# 3DPrinter-mainboard.net
KiCad netlist of a schematic drawn in EAGLE
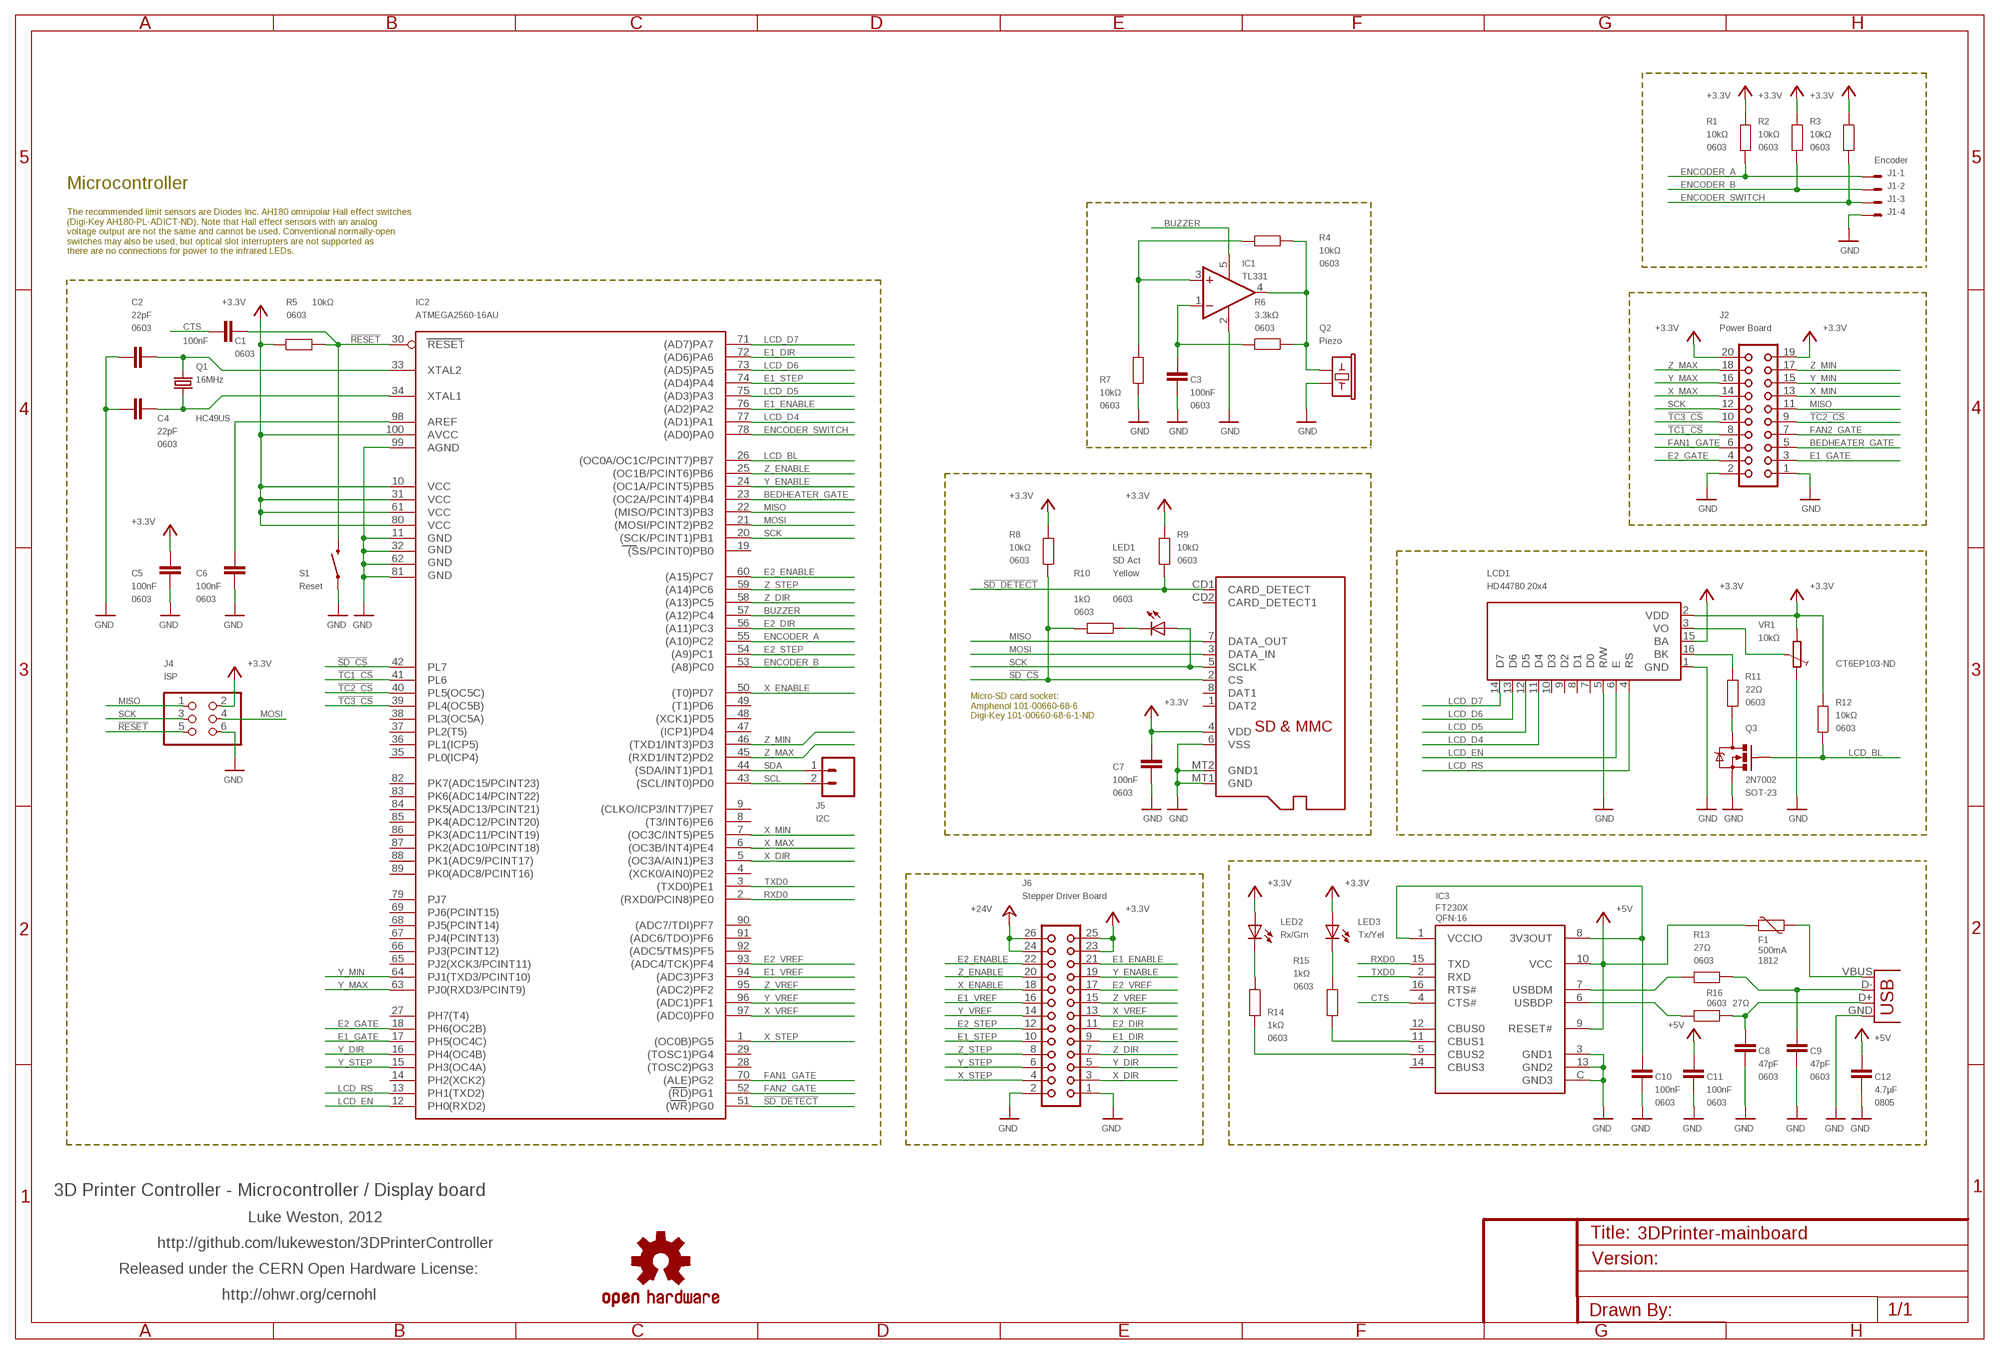
[diagram p0: schematic, sheet 1]

(export (version "E")
  (design (tool "Eeschema 10.0.6"))
  (components
    (comp (ref "C1")
      (value "100nF")
      (footprint "eagle-import:0603")
      (fields (field (name "PACKAGE") "0603"))
      (libsource (lib "eagle-import") (part "CAP0603"))
    )
    (comp (ref "C2")
      (value "22pF")
      (footprint "eagle-import:0603")
      (fields (field (name "PACKAGE") "0603"))
      (libsource (lib "eagle-import") (part "CAP0603"))
    )
    (comp (ref "C3")
      (value "100nF")
      (footprint "eagle-import:0603")
      (fields (field (name "PACKAGE") "0603"))
      (libsource (lib "eagle-import") (part "CAP0603"))
    )
    (comp (ref "C4")
      (value "22pF")
      (footprint "eagle-import:0603")
      (fields (field (name "PACKAGE") "0603"))
      (libsource (lib "eagle-import") (part "CAP0603"))
    )
    (comp (ref "C5")
      (value "100nF")
      (footprint "eagle-import:0603")
      (fields (field (name "PACKAGE") "0603"))
      (libsource (lib "eagle-import") (part "CAP0603"))
    )
    (comp (ref "C6")
      (value "100nF")
      (footprint "eagle-import:0603")
      (fields (field (name "PACKAGE") "0603"))
      (libsource (lib "eagle-import") (part "CAP0603"))
    )
    (comp (ref "C7")
      (value "100nF")
      (footprint "eagle-import:0603")
      (fields (field (name "PACKAGE") "0603"))
      (libsource (lib "eagle-import") (part "CAP0603"))
    )
    (comp (ref "C8")
      (value "47pF")
      (footprint "eagle-import:0603")
      (fields (field (name "PACKAGE") "0603"))
      (libsource (lib "eagle-import") (part "CAP0603"))
    )
    (comp (ref "C9")
      (value "47pF")
      (footprint "eagle-import:0603")
      (fields (field (name "PACKAGE") "0603"))
      (libsource (lib "eagle-import") (part "CAP0603"))
    )
    (comp (ref "C10")
      (value "100nF")
      (footprint "eagle-import:0603")
      (fields (field (name "PACKAGE") "0603"))
      (libsource (lib "eagle-import") (part "CAP0603"))
    )
    (comp (ref "C11")
      (value "100nF")
      (footprint "eagle-import:0603")
      (fields (field (name "PACKAGE") "0603"))
      (libsource (lib "eagle-import") (part "CAP0603"))
    )
    (comp (ref "C12")
      (value "4.7µF")
      (footprint "eagle-import:0805")
      (fields (field (name "PACKAGE") "0805"))
      (libsource (lib "eagle-import") (part "CAP0805"))
    )
    (comp (ref "F1")
      (value "500mA")
      (footprint "eagle-import:1812")
      (fields (field (name "PACKAGE") "1812"))
      (libsource (lib "eagle-import") (part "PTC"))
    )
    (comp (ref "IC1")
      (value "TL331")
      (footprint "eagle-import:DBV-R-PDSO-G5")
      (libsource (lib "eagle-import") (part "TL331"))
    )
    (comp (ref "IC2")
      (value "ATMEGA2560-16AU")
      (footprint "eagle-import:TQFP100")
      (libsource (lib "eagle-import") (part "ATMEGAAU1280-16"))
    )
    (comp (ref "IC3")
      (value "FT230X")
      (footprint "eagle-import:QFN4X4-16")
      (fields (field (name "PACKAGE") "QFN-16"))
      (libsource (lib "eagle-import") (part "FT230XQ"))
    )
    (comp (ref "J1")
      (value "Encoder")
      (footprint "eagle-import:7395-04")
      (libsource (lib "eagle-import") (part "22-?-0405-7048"))
    )
    (comp (ref "J2")
      (value "Power Board")
      (footprint "eagle-import:CON20L")
      (fields (field (name "OC_FARNELL") "unknown") (field (name "OC_NEWARK") "unknown"))
      (libsource (lib "eagle-import") (part "CON20L"))
    )
    (comp (ref "J3")
      (value "MicroSD Card")
      (footprint "eagle-import:ADAFRUIT_MICROSD")
      (libsource (lib "eagle-import") (part "ADAFRUIT_MICROSD"))
    )
    (comp (ref "J4")
      (value "ISP")
      (footprint "eagle-import:2X03")
      (libsource (lib "eagle-import") (part "PINHD-2X3"))
    )
    (comp (ref "J5")
      (value "I2C")
      (footprint "eagle-import:1X02")
      (libsource (lib "eagle-import") (part "M02PTH"))
    )
    (comp (ref "J6")
      (value "Stepper Driver Board")
      (footprint "eagle-import:CON26L")
      (libsource (lib "eagle-import") (part "CON26L"))
    )
    (comp (ref "LCD1")
      (value "HD44780 20x4")
      (footprint "eagle-import:HDM20416L")
      (libsource (lib "eagle-import") (part "HDM20416L"))
    )
    (comp (ref "LED1")
      (value "SD Act")
      (footprint "eagle-import:LED-0603")
      (fields (field (name "COLOUR") "Yellow") (field (name "PACKAGE") "0603"))
      (libsource (lib "eagle-import") (part "LED0603"))
    )
    (comp (ref "LED2")
      (value "Rx/Grn")
      (footprint "eagle-import:LED-0603")
      (libsource (lib "eagle-import") (part "LED0603"))
    )
    (comp (ref "LED3")
      (value "Tx/Yel")
      (footprint "eagle-import:LED-0603")
      (libsource (lib "eagle-import") (part "LED0603"))
    )
    (comp (ref "Q1")
      (value "16MHz")
      (footprint "eagle-import:HC49US")
      (fields (field (name "PACKAGE") "HC49US"))
      (libsource (lib "eagle-import") (part "CRYSTALHC49US"))
    )
    (comp (ref "Q2")
      (value "Piezo")
      (footprint "eagle-import:FREETRONICS-MASTER-V1_BUZZER-12X12-SMT")
      (libsource (lib "eagle-import") (part "FREETRONICS-MASTER-V1_BUZZERSMD12X12"))
    )
    (comp (ref "Q3")
      (value "2N7002")
      (footprint "eagle-import:SOT23-3")
      (fields (field (name "PACKAGE") "SOT-23"))
      (libsource (lib "eagle-import") (part "MOSFET-NCHANNELSMD"))
    )
    (comp (ref "R1")
      (value "10kΩ")
      (footprint "eagle-import:0603")
      (fields (field (name "PACKAGE") "0603"))
      (libsource (lib "eagle-import") (part "RESISTOR0603"))
    )
    (comp (ref "R2")
      (value "10kΩ")
      (footprint "eagle-import:0603")
      (fields (field (name "PACKAGE") "0603"))
      (libsource (lib "eagle-import") (part "RESISTOR0603"))
    )
    (comp (ref "R3")
      (value "10kΩ")
      (footprint "eagle-import:0603")
      (fields (field (name "PACKAGE") "0603"))
      (libsource (lib "eagle-import") (part "RESISTOR0603"))
    )
    (comp (ref "R4")
      (value "10kΩ")
      (footprint "eagle-import:0603")
      (fields (field (name "PACKAGE") "0603"))
      (libsource (lib "eagle-import") (part "RESISTOR0603"))
    )
    (comp (ref "R5")
      (value "10kΩ")
      (footprint "eagle-import:0603")
      (fields (field (name "PACKAGE") "0603"))
      (libsource (lib "eagle-import") (part "RESISTOR0603"))
    )
    (comp (ref "R6")
      (value "3.3kΩ")
      (footprint "eagle-import:0603")
      (fields (field (name "PACKAGE") "0603"))
      (libsource (lib "eagle-import") (part "RESISTOR0603"))
    )
    (comp (ref "R7")
      (value "10kΩ")
      (footprint "eagle-import:0603")
      (fields (field (name "PACKAGE") "0603"))
      (libsource (lib "eagle-import") (part "RESISTOR0603"))
    )
    (comp (ref "R8")
      (value "10kΩ")
      (footprint "eagle-import:0603")
      (fields (field (name "PACKAGE") "0603"))
      (libsource (lib "eagle-import") (part "RESISTOR0603"))
    )
    (comp (ref "R9")
      (value "10kΩ")
      (footprint "eagle-import:0603")
      (fields (field (name "PACKAGE") "0603"))
      (libsource (lib "eagle-import") (part "RESISTOR0603"))
    )
    (comp (ref "R10")
      (value "1kΩ")
      (footprint "eagle-import:0603")
      (fields (field (name "PACKAGE") "0603"))
      (libsource (lib "eagle-import") (part "RESISTOR0603"))
    )
    (comp (ref "R11")
      (value "22Ω")
      (footprint "eagle-import:0603")
      (fields (field (name "PACKAGE") "0603"))
      (libsource (lib "eagle-import") (part "RESISTOR0603"))
    )
    (comp (ref "R12")
      (value "10kΩ")
      (footprint "eagle-import:0603")
      (fields (field (name "PACKAGE") "0603"))
      (libsource (lib "eagle-import") (part "RESISTOR0603"))
    )
    (comp (ref "R13")
      (value "27Ω")
      (footprint "eagle-import:0603")
      (fields (field (name "PACKAGE") "0603"))
      (libsource (lib "eagle-import") (part "RESISTOR0603"))
    )
    (comp (ref "R14")
      (value "1kΩ")
      (footprint "eagle-import:0603")
      (fields (field (name "PACKAGE") "0603"))
      (libsource (lib "eagle-import") (part "RESISTOR0603"))
    )
    (comp (ref "R15")
      (value "1kΩ")
      (footprint "eagle-import:0603")
      (fields (field (name "PACKAGE") "0603"))
      (libsource (lib "eagle-import") (part "RESISTOR0603"))
    )
    (comp (ref "R16")
      (value "27Ω")
      (footprint "eagle-import:0603")
      (fields (field (name "PACKAGE") "0603"))
      (libsource (lib "eagle-import") (part "RESISTOR0603"))
    )
    (comp (ref "S1")
      (value "Reset")
      (footprint "eagle-import:TACTILE_SWITCH_SMD")
      (libsource (lib "eagle-import") (part "SWITCH-MOMENTARY-2SMD"))
    )
    (comp (ref "SY")
      (value "OSHW-LOGOS")
      (footprint "eagle-import:OSHW-LOGO-S")
      (libsource (lib "eagle-import") (part "OSHW-LOGOS"))
    )
    (comp (ref "VR1")
      (value "10kΩ")
      (footprint "eagle-import:CT6")
      (fields (field (name "SKU") "CT6EP103-ND"))
      (libsource (lib "eagle-import") (part "TRIM_EU-CT6"))
    )
    (comp (ref "X1")
      (value "USB-MICROB")
      (footprint "eagle-import:USB-MICROB")
      (libsource (lib "eagle-import") (part "USB-MICROB"))
    )
  )
  (nets
    (net (code "1") (name "+3.3V") (class "Default")
      (node (ref "C5") (pin "1") (pinfunction "1_1") (pintype "passive"))
      (node (ref "C7") (pin "1") (pinfunction "1_1") (pintype "passive"))
      (node (ref "IC2") (pin "10") (pinfunction "VCC_10") (pintype "power_in"))
      (node (ref "IC2") (pin "100") (pinfunction "AVCC_100") (pintype "power_in"))
      (node (ref "IC2") (pin "31") (pinfunction "VCC1_31") (pintype "power_in"))
      (node (ref "IC2") (pin "61") (pinfunction "VCC2_61") (pintype "power_in"))
      (node (ref "IC2") (pin "80") (pinfunction "VCC3_80") (pintype "power_in"))
      (node (ref "J2") (pin "19") (pinfunction "19_19") (pintype "passive"))
      (node (ref "J2") (pin "20") (pinfunction "20_20") (pintype "passive"))
      (node (ref "J3") (pin "4") (pinfunction "VDD_4") (pintype "power_in"))
      (node (ref "J4") (pin "2") (pinfunction "2_2") (pintype "passive"))
      (node (ref "J6") (pin "23") (pinfunction "23_23") (pintype "passive"))
      (node (ref "J6") (pin "25") (pinfunction "25_25") (pintype "passive"))
      (node (ref "LCD1") (pin "15") (pinfunction "BA_15") (pintype "bidirectional"))
      (node (ref "LCD1") (pin "2") (pinfunction "VDD_2") (pintype "bidirectional"))
      (node (ref "LED2") (pin "A") (pinfunction "A_A") (pintype "passive"))
      (node (ref "LED3") (pin "A") (pinfunction "A_A") (pintype "passive"))
      (node (ref "R1") (pin "1") (pinfunction "1_1") (pintype "passive"))
      (node (ref "R12") (pin "1") (pinfunction "1_1") (pintype "passive"))
      (node (ref "R2") (pin "1") (pinfunction "1_1") (pintype "passive"))
      (node (ref "R3") (pin "1") (pinfunction "1_1") (pintype "passive"))
      (node (ref "R5") (pin "1") (pinfunction "1_1") (pintype "passive"))
      (node (ref "R8") (pin "1") (pinfunction "1_1") (pintype "passive"))
      (node (ref "R9") (pin "1") (pinfunction "1_1") (pintype "passive"))
      (node (ref "VR1") (pin "A") (pinfunction "A_A") (pintype "passive"))
    )
    (net (code "2") (name "+5V") (class "Default")
      (node (ref "C11") (pin "1") (pinfunction "1_1") (pintype "passive"))
      (node (ref "C12") (pin "1") (pinfunction "1_1") (pintype "passive"))
      (node (ref "F1") (pin "2") (pinfunction "P$2_2") (pintype "bidirectional"))
      (node (ref "IC3") (pin "10") (pinfunction "VCC_10") (pintype "power_in"))
      (node (ref "IC3") (pin "9") (pinfunction "RESET#_9") (pintype "input"))
    )
    (net (code "3") (name "+24V") (class "Default")
      (node (ref "J6") (pin "24") (pinfunction "24_24") (pintype "passive"))
      (node (ref "J6") (pin "26") (pinfunction "26_26") (pintype "passive"))
    )
    (net (code "4") (name "/BEDHEATER_GATE") (class "Default")
      (node (ref "IC2") (pin "23") (pinfunction "(OC2A/PCINT4)PB4_23") (pintype "bidirectional"))
      (node (ref "J2") (pin "5") (pinfunction "5_5") (pintype "passive"))
    )
    (net (code "5") (name "/BUZZER") (class "Default")
      (node (ref "IC1") (pin "5") (pinfunction "V+_5") (pintype "power_in"))
      (node (ref "IC2") (pin "57") (pinfunction "(A12)PC4_57") (pintype "bidirectional"))
    )
    (net (code "6") (name "/CTS") (class "Default")
      (node (ref "C1") (pin "1") (pinfunction "1_1") (pintype "passive"))
      (node (ref "IC3") (pin "4") (pinfunction "CTS#_4") (pintype "bidirectional"))
    )
    (net (code "7") (name "/E1_DIR") (class "Default")
      (node (ref "IC2") (pin "72") (pinfunction "(AD6)PA6_72") (pintype "bidirectional"))
      (node (ref "J6") (pin "9") (pinfunction "9_9") (pintype "passive"))
    )
    (net (code "8") (name "/E1_ENABLE") (class "Default")
      (node (ref "IC2") (pin "76") (pinfunction "(AD2)PA2_76") (pintype "bidirectional"))
      (node (ref "J6") (pin "21") (pinfunction "21_21") (pintype "passive"))
    )
    (net (code "9") (name "/E1_GATE") (class "Default")
      (node (ref "IC2") (pin "17") (pinfunction "PH5(OC4C)_17") (pintype "bidirectional"))
      (node (ref "J2") (pin "3") (pinfunction "3_3") (pintype "passive"))
    )
    (net (code "10") (name "/E1_STEP") (class "Default")
      (node (ref "IC2") (pin "74") (pinfunction "(AD4)PA4_74") (pintype "bidirectional"))
      (node (ref "J6") (pin "10") (pinfunction "10_10") (pintype "passive"))
    )
    (net (code "11") (name "/E1_VREF") (class "Default")
      (node (ref "IC2") (pin "94") (pinfunction "(ADC3)PF3_94") (pintype "bidirectional"))
      (node (ref "J6") (pin "16") (pinfunction "16_16") (pintype "passive"))
    )
    (net (code "12") (name "/E2_DIR") (class "Default")
      (node (ref "IC2") (pin "56") (pinfunction "(A11)PC3_56") (pintype "bidirectional"))
      (node (ref "J6") (pin "11") (pinfunction "11_11") (pintype "passive"))
    )
    (net (code "13") (name "/E2_ENABLE") (class "Default")
      (node (ref "IC2") (pin "60") (pinfunction "(A15)PC7_60") (pintype "bidirectional"))
      (node (ref "J6") (pin "22") (pinfunction "22_22") (pintype "passive"))
    )
    (net (code "14") (name "/E2_GATE") (class "Default")
      (node (ref "IC2") (pin "18") (pinfunction "PH6(OC2B)_18") (pintype "bidirectional"))
      (node (ref "J2") (pin "4") (pinfunction "4_4") (pintype "passive"))
    )
    (net (code "15") (name "/E2_STEP") (class "Default")
      (node (ref "IC2") (pin "54") (pinfunction "(A9)PC1_54") (pintype "bidirectional"))
      (node (ref "J6") (pin "12") (pinfunction "12_12") (pintype "passive"))
    )
    (net (code "16") (name "/E2_VREF") (class "Default")
      (node (ref "IC2") (pin "93") (pinfunction "(ADC4/TCK)PF4_93") (pintype "bidirectional"))
      (node (ref "J6") (pin "17") (pinfunction "17_17") (pintype "passive"))
    )
    (net (code "17") (name "/ENCODER_A") (class "Default")
      (node (ref "IC2") (pin "55") (pinfunction "(A10)PC2_55") (pintype "bidirectional"))
      (node (ref "J1") (pin "1") (pinfunction "S_1") (pintype "passive"))
      (node (ref "R1") (pin "2") (pinfunction "2_2") (pintype "passive"))
    )
    (net (code "18") (name "/ENCODER_B") (class "Default")
      (node (ref "IC2") (pin "53") (pinfunction "(A8)PC0_53") (pintype "bidirectional"))
      (node (ref "J1") (pin "2") (pinfunction "S_2") (pintype "passive"))
      (node (ref "R2") (pin "2") (pinfunction "2_2") (pintype "passive"))
    )
    (net (code "19") (name "/ENCODER_SWITCH") (class "Default")
      (node (ref "IC2") (pin "78") (pinfunction "(AD0)PA0_78") (pintype "bidirectional"))
      (node (ref "J1") (pin "3") (pinfunction "S_3") (pintype "passive"))
      (node (ref "R3") (pin "2") (pinfunction "2_2") (pintype "passive"))
    )
    (net (code "20") (name "/FAN1_GATE") (class "Default")
      (node (ref "IC2") (pin "70") (pinfunction "(ALE)PG2_70") (pintype "bidirectional"))
      (node (ref "J2") (pin "6") (pinfunction "6_6") (pintype "passive"))
    )
    (net (code "21") (name "/FAN2_GATE") (class "Default")
      (node (ref "IC2") (pin "52") (pinfunction "(RD)PG1_52") (pintype "bidirectional"))
      (node (ref "J2") (pin "7") (pinfunction "7_7") (pintype "passive"))
    )
    (net (code "22") (name "/LCD_BL") (class "Default")
      (node (ref "IC2") (pin "26") (pinfunction "(OC0A/OC1C/PCINT7)PB7_26") (pintype "bidirectional"))
      (node (ref "Q3") (pin "1") (pinfunction "G_1") (pintype "passive"))
      (node (ref "R12") (pin "2") (pinfunction "2_2") (pintype "passive"))
    )
    (net (code "23") (name "/LCD_D4") (class "Default")
      (node (ref "IC2") (pin "77") (pinfunction "(AD1)PA1_77") (pintype "bidirectional"))
      (node (ref "LCD1") (pin "11") (pinfunction "D4_11") (pintype "bidirectional"))
    )
    (net (code "24") (name "/LCD_D5") (class "Default")
      (node (ref "IC2") (pin "75") (pinfunction "(AD3)PA3_75") (pintype "bidirectional"))
      (node (ref "LCD1") (pin "12") (pinfunction "D5_12") (pintype "bidirectional"))
    )
    (net (code "25") (name "/LCD_D6") (class "Default")
      (node (ref "IC2") (pin "73") (pinfunction "(AD5)PA5_73") (pintype "bidirectional"))
      (node (ref "LCD1") (pin "13") (pinfunction "D6_13") (pintype "bidirectional"))
    )
    (net (code "26") (name "/LCD_D7") (class "Default")
      (node (ref "IC2") (pin "71") (pinfunction "(AD7)PA7_71") (pintype "bidirectional"))
      (node (ref "LCD1") (pin "14") (pinfunction "D7_14") (pintype "bidirectional"))
    )
    (net (code "27") (name "/LCD_EN") (class "Default")
      (node (ref "IC2") (pin "12") (pinfunction "PH0(RXD2)_12") (pintype "bidirectional"))
      (node (ref "LCD1") (pin "6") (pinfunction "E_6") (pintype "bidirectional"))
    )
    (net (code "28") (name "/LCD_RS") (class "Default")
      (node (ref "IC2") (pin "13") (pinfunction "PH1(TXD2)_13") (pintype "bidirectional"))
      (node (ref "LCD1") (pin "4") (pinfunction "RS_4") (pintype "bidirectional"))
    )
    (net (code "29") (name "/MISO") (class "Default")
      (node (ref "IC2") (pin "22") (pinfunction "(MISO/PCINT3)PB3_22") (pintype "bidirectional"))
      (node (ref "J2") (pin "11") (pinfunction "11_11") (pintype "passive"))
      (node (ref "J3") (pin "7") (pinfunction "DATA_OUT_7") (pintype "output"))
      (node (ref "J4") (pin "1") (pinfunction "1_1") (pintype "passive"))
    )
    (net (code "30") (name "/MOSI") (class "Default")
      (node (ref "IC2") (pin "21") (pinfunction "(MOSI/PCINT2)PB2_21") (pintype "bidirectional"))
      (node (ref "J3") (pin "3") (pinfunction "DATA_IN_3") (pintype "input"))
      (node (ref "J4") (pin "4") (pinfunction "4_4") (pintype "passive"))
    )
    (net (code "31") (name "/RXD0") (class "Default")
      (node (ref "IC2") (pin "2") (pinfunction "(RXD0/PCIN8)PE0_2") (pintype "bidirectional"))
      (node (ref "IC3") (pin "15") (pinfunction "TXD_15") (pintype "output"))
    )
    (net (code "32") (name "/SCK") (class "Default")
      (node (ref "IC2") (pin "20") (pinfunction "(SCK/PCINT1)PB1_20") (pintype "bidirectional"))
      (node (ref "J2") (pin "12") (pinfunction "12_12") (pintype "passive"))
      (node (ref "J3") (pin "5") (pinfunction "SCLK_5") (pintype "input"))
      (node (ref "J4") (pin "3") (pinfunction "3_3") (pintype "passive"))
      (node (ref "LED1") (pin "A") (pinfunction "A_A") (pintype "passive"))
    )
    (net (code "33") (name "/SCL") (class "Default")
      (node (ref "IC2") (pin "43") (pinfunction "(SCL/INT0)PD0_43") (pintype "bidirectional"))
      (node (ref "J5") (pin "2") (pinfunction "2_2") (pintype "passive"))
    )
    (net (code "34") (name "/SDA") (class "Default")
      (node (ref "IC2") (pin "44") (pinfunction "(SDA/INT1)PD1_44") (pintype "bidirectional"))
      (node (ref "J5") (pin "1") (pinfunction "1_1") (pintype "passive"))
    )
    (net (code "35") (name "/TXD0") (class "Default")
      (node (ref "IC2") (pin "3") (pinfunction "(TXD0)PE1_3") (pintype "bidirectional"))
      (node (ref "IC3") (pin "2") (pinfunction "RXD_2") (pintype "input"))
    )
    (net (code "36") (name "/X_DIR") (class "Default")
      (node (ref "IC2") (pin "5") (pinfunction "(OC3A/AIN1)PE3_5") (pintype "bidirectional"))
      (node (ref "J6") (pin "3") (pinfunction "3_3") (pintype "passive"))
    )
    (net (code "37") (name "/X_ENABLE") (class "Default")
      (node (ref "IC2") (pin "50") (pinfunction "(T0)PD7_50") (pintype "bidirectional"))
      (node (ref "J6") (pin "18") (pinfunction "18_18") (pintype "passive"))
    )
    (net (code "38") (name "/X_MAX") (class "Default")
      (node (ref "IC2") (pin "6") (pinfunction "(OC3B/INT4)PE4_6") (pintype "bidirectional"))
      (node (ref "J2") (pin "14") (pinfunction "14_14") (pintype "passive"))
    )
    (net (code "39") (name "/X_MIN") (class "Default")
      (node (ref "IC2") (pin "7") (pinfunction "(OC3C/INT5)PE5_7") (pintype "bidirectional"))
      (node (ref "J2") (pin "13") (pinfunction "13_13") (pintype "passive"))
    )
    (net (code "40") (name "/X_STEP") (class "Default")
      (node (ref "IC2") (pin "1") (pinfunction "(OC0B)PG5_1") (pintype "bidirectional"))
      (node (ref "J6") (pin "4") (pinfunction "4_4") (pintype "passive"))
    )
    (net (code "41") (name "/X_VREF") (class "Default")
      (node (ref "IC2") (pin "97") (pinfunction "(ADC0)PF0_97") (pintype "bidirectional"))
      (node (ref "J6") (pin "13") (pinfunction "13_13") (pintype "passive"))
    )
    (net (code "42") (name "/Y_DIR") (class "Default")
      (node (ref "IC2") (pin "16") (pinfunction "PH4(OC4B)_16") (pintype "bidirectional"))
      (node (ref "J6") (pin "5") (pinfunction "5_5") (pintype "passive"))
    )
    (net (code "43") (name "/Y_ENABLE") (class "Default")
      (node (ref "IC2") (pin "24") (pinfunction "(OC1A/PCINT5)PB5_24") (pintype "bidirectional"))
      (node (ref "J6") (pin "19") (pinfunction "19_19") (pintype "passive"))
    )
    (net (code "44") (name "/Y_MAX") (class "Default")
      (node (ref "IC2") (pin "63") (pinfunction "PJ0(RXD3/PCINT9)_63") (pintype "bidirectional"))
      (node (ref "J2") (pin "16") (pinfunction "16_16") (pintype "passive"))
    )
    (net (code "45") (name "/Y_MIN") (class "Default")
      (node (ref "IC2") (pin "64") (pinfunction "PJ1(TXD3/PCINT10)_64") (pintype "bidirectional"))
      (node (ref "J2") (pin "15") (pinfunction "15_15") (pintype "passive"))
    )
    (net (code "46") (name "/Y_STEP") (class "Default")
      (node (ref "IC2") (pin "15") (pinfunction "PH3(OC4A)_15") (pintype "bidirectional"))
      (node (ref "J6") (pin "6") (pinfunction "6_6") (pintype "passive"))
    )
    (net (code "47") (name "/Y_VREF") (class "Default")
      (node (ref "IC2") (pin "96") (pinfunction "(ADC1)PF1_96") (pintype "bidirectional"))
      (node (ref "J6") (pin "14") (pinfunction "14_14") (pintype "passive"))
    )
    (net (code "48") (name "/Z_DIR") (class "Default")
      (node (ref "IC2") (pin "58") (pinfunction "(A13)PC5_58") (pintype "bidirectional"))
      (node (ref "J6") (pin "7") (pinfunction "7_7") (pintype "passive"))
    )
    (net (code "49") (name "/Z_ENABLE") (class "Default")
      (node (ref "IC2") (pin "25") (pinfunction "(OC1B/PCINT6)PB6_25") (pintype "bidirectional"))
      (node (ref "J6") (pin "20") (pinfunction "20_20") (pintype "passive"))
    )
    (net (code "50") (name "/Z_MAX") (class "Default")
      (node (ref "IC2") (pin "45") (pinfunction "(RXD1/INT2)PD2_45") (pintype "bidirectional"))
      (node (ref "J2") (pin "18") (pinfunction "18_18") (pintype "passive"))
    )
    (net (code "51") (name "/Z_MIN") (class "Default")
      (node (ref "IC2") (pin "46") (pinfunction "(TXD1/INT3)PD3_46") (pintype "bidirectional"))
      (node (ref "J2") (pin "17") (pinfunction "17_17") (pintype "passive"))
    )
    (net (code "52") (name "/Z_STEP") (class "Default")
      (node (ref "IC2") (pin "59") (pinfunction "(A14)PC6_59") (pintype "bidirectional"))
      (node (ref "J6") (pin "8") (pinfunction "8_8") (pintype "passive"))
    )
    (net (code "53") (name "/Z_VREF") (class "Default")
      (node (ref "IC2") (pin "95") (pinfunction "(ADC2)PF2_95") (pintype "bidirectional"))
      (node (ref "J6") (pin "15") (pinfunction "15_15") (pintype "passive"))
    )
    (net (code "54") (name "/~{RESET}") (class "Default")
      (node (ref "C1") (pin "2") (pinfunction "2_2") (pintype "passive"))
      (node (ref "IC2") (pin "30") (pinfunction "RESET_30") (pintype "input"))
      (node (ref "J4") (pin "5") (pinfunction "5_5") (pintype "passive"))
      (node (ref "R5") (pin "2") (pinfunction "2_2") (pintype "passive"))
      (node (ref "S1") (pin "3") (pinfunction "2_3") (pintype "passive"))
    )
    (net (code "55") (name "/~{SD_CS}") (class "Default")
      (node (ref "IC2") (pin "42") (pinfunction "PL7_42") (pintype "bidirectional"))
      (node (ref "J3") (pin "2") (pinfunction "CS_2") (pintype "input"))
      (node (ref "R10") (pin "2") (pinfunction "2_2") (pintype "passive"))
      (node (ref "R8") (pin "2") (pinfunction "2_2") (pintype "passive"))
    )
    (net (code "56") (name "/~{SD_DETECT}") (class "Default")
      (node (ref "IC2") (pin "51") (pinfunction "(WR)PG0_51") (pintype "bidirectional"))
      (node (ref "J3") (pin "CD1") (pinfunction "CARD_DETECT_CD1") (pintype "passive"))
      (node (ref "R9") (pin "2") (pinfunction "2_2") (pintype "passive"))
    )
    (net (code "57") (name "/~{TC1_CS}") (class "Default")
      (node (ref "IC2") (pin "41") (pinfunction "PL6_41") (pintype "bidirectional"))
      (node (ref "J2") (pin "8") (pinfunction "8_8") (pintype "passive"))
    )
    (net (code "58") (name "/~{TC2_CS}") (class "Default")
      (node (ref "IC2") (pin "40") (pinfunction "PL5(OC5C)_40") (pintype "bidirectional"))
      (node (ref "J2") (pin "9") (pinfunction "9_9") (pintype "passive"))
    )
    (net (code "59") (name "/~{TC3_CS}") (class "Default")
      (node (ref "IC2") (pin "39") (pinfunction "PL4(OC5B)_39") (pintype "bidirectional"))
      (node (ref "J2") (pin "10") (pinfunction "10_10") (pintype "passive"))
    )
    (net (code "60") (name "GND") (class "Default")
      (node (ref "C10") (pin "2") (pinfunction "2_2") (pintype "passive"))
      (node (ref "C11") (pin "2") (pinfunction "2_2") (pintype "passive"))
      (node (ref "C12") (pin "2") (pinfunction "2_2") (pintype "passive"))
      (node (ref "C2") (pin "1") (pinfunction "1_1") (pintype "passive"))
      (node (ref "C3") (pin "2") (pinfunction "2_2") (pintype "passive"))
      (node (ref "C4") (pin "1") (pinfunction "1_1") (pintype "passive"))
      (node (ref "C5") (pin "2") (pinfunction "2_2") (pintype "passive"))
      (node (ref "C6") (pin "2") (pinfunction "2_2") (pintype "passive"))
      (node (ref "C7") (pin "2") (pinfunction "2_2") (pintype "passive"))
      (node (ref "C8") (pin "2") (pinfunction "2_2") (pintype "passive"))
      (node (ref "C9") (pin "2") (pinfunction "2_2") (pintype "passive"))
      (node (ref "IC1") (pin "2") (pinfunction "GND_2") (pintype "power_in"))
      (node (ref "IC2") (pin "11") (pinfunction "GND_11") (pintype "power_in"))
      (node (ref "IC2") (pin "32") (pinfunction "GND1_32") (pintype "power_in"))
      (node (ref "IC2") (pin "62") (pinfunction "GND2_62") (pintype "power_in"))
      (node (ref "IC2") (pin "81") (pinfunction "GND3_81") (pintype "power_in"))
      (node (ref "IC2") (pin "99") (pinfunction "AGND_99") (pintype "power_in"))
      (node (ref "IC3") (pin "13") (pinfunction "GND2_13") (pintype "power_in"))
      (node (ref "IC3") (pin "3") (pinfunction "GND1_3") (pintype "power_in"))
      (node (ref "IC3") (pin "C") (pinfunction "GND3_C") (pintype "power_in"))
      (node (ref "J1") (pin "4") (pinfunction "S_4") (pintype "passive"))
      (node (ref "J2") (pin "1") (pinfunction "1_1") (pintype "passive"))
      (node (ref "J2") (pin "2") (pinfunction "2_2") (pintype "passive"))
      (node (ref "J3") (pin "6") (pinfunction "VSS_6") (pintype "power_in"))
      (node (ref "J3") (pin "MT1") (pinfunction "GND_MT1") (pintype "power_in"))
      (node (ref "J3") (pin "MT2") (pinfunction "GND1_MT2") (pintype "power_in"))
      (node (ref "J4") (pin "6") (pinfunction "6_6") (pintype "passive"))
      (node (ref "J6") (pin "1") (pinfunction "1_1") (pintype "passive"))
      (node (ref "J6") (pin "2") (pinfunction "2_2") (pintype "passive"))
      (node (ref "LCD1") (pin "1") (pinfunction "GND_1") (pintype "bidirectional"))
      (node (ref "LCD1") (pin "5") (pinfunction "R/W_5") (pintype "bidirectional"))
      (node (ref "Q2") (pin "1") (pinfunction "1_1") (pintype "passive"))
      (node (ref "Q3") (pin "2") (pinfunction "S_2") (pintype "passive"))
      (node (ref "R7") (pin "1") (pinfunction "1_1") (pintype "passive"))
      (node (ref "S1") (pin "1") (pinfunction "1_1") (pintype "passive"))
      (node (ref "VR1") (pin "E") (pinfunction "E_E") (pintype "passive"))
      (node (ref "X1") (pin "GND") (pinfunction "GND_GND") (pintype "bidirectional"))
    )
    (net (code "61") (name "Net-(C8-Pad1)") (class "Default")
      (node (ref "C8") (pin "1") (pinfunction "1_1") (pintype "passive"))
      (node (ref "R16") (pin "2") (pinfunction "2_2") (pintype "passive"))
      (node (ref "X1") (pin "D+") (pinfunction "D+_D+") (pintype "bidirectional"))
    )
    (net (code "62") (name "Net-(C9-Pad1)") (class "Default")
      (node (ref "C9") (pin "1") (pinfunction "1_1") (pintype "passive"))
      (node (ref "R13") (pin "2") (pinfunction "2_2") (pintype "passive"))
      (node (ref "X1") (pin "D-") (pinfunction "D-_D-") (pintype "bidirectional"))
    )
    (net (code "63") (name "Net-(F1-P$1)") (class "Default")
      (node (ref "F1") (pin "1") (pinfunction "P$1_1") (pintype "bidirectional"))
      (node (ref "X1") (pin "VBUS") (pinfunction "VBUS_VBUS") (pintype "bidirectional"))
    )
    (net (code "64") (name "Net-(IC1-+IN)") (class "Default")
      (node (ref "IC1") (pin "3") (pinfunction "+IN_3") (pintype "input"))
      (node (ref "R4") (pin "2") (pinfunction "2_2") (pintype "passive"))
      (node (ref "R7") (pin "2") (pinfunction "2_2") (pintype "passive"))
    )
    (net (code "65") (name "Net-(IC1--IN)") (class "Default")
      (node (ref "C3") (pin "1") (pinfunction "1_1") (pintype "passive"))
      (node (ref "IC1") (pin "1") (pinfunction "-IN_1") (pintype "input"))
      (node (ref "R6") (pin "2") (pinfunction "2_2") (pintype "passive"))
    )
    (net (code "66") (name "Net-(IC1-OUT)") (class "Default")
      (node (ref "IC1") (pin "4") (pinfunction "OUT_4") (pintype "output"))
      (node (ref "Q2") (pin "2") (pinfunction "2_2") (pintype "passive"))
      (node (ref "R4") (pin "1") (pinfunction "1_1") (pintype "passive"))
      (node (ref "R6") (pin "1") (pinfunction "1_1") (pintype "passive"))
    )
    (net (code "67") (name "Net-(IC2-AREF)") (class "Default")
      (node (ref "C6") (pin "1") (pinfunction "1_1") (pintype "passive"))
      (node (ref "IC2") (pin "98") (pinfunction "AREF_98") (pintype "bidirectional"))
    )
    (net (code "68") (name "Net-(IC2-XTAL1)") (class "Default")
      (node (ref "C4") (pin "2") (pinfunction "2_2") (pintype "passive"))
      (node (ref "IC2") (pin "34") (pinfunction "XTAL1_34") (pintype "input"))
      (node (ref "Q1") (pin "1") (pinfunction "1_1") (pintype "passive"))
    )
    (net (code "69") (name "Net-(IC2-XTAL2)") (class "Default")
      (node (ref "C2") (pin "2") (pinfunction "2_2") (pintype "passive"))
      (node (ref "IC2") (pin "33") (pinfunction "XTAL2_33") (pintype "output"))
      (node (ref "Q1") (pin "2") (pinfunction "2_2") (pintype "passive"))
    )
    (net (code "70") (name "Net-(IC3-3V3OUT)") (class "Default")
      (node (ref "C10") (pin "1") (pinfunction "1_1") (pintype "passive"))
      (node (ref "IC3") (pin "1") (pinfunction "VCCIO_1") (pintype "input"))
      (node (ref "IC3") (pin "8") (pinfunction "3V3OUT_8") (pintype "output"))
    )
    (net (code "71") (name "Net-(IC3-CBUS1)") (class "Default")
      (node (ref "IC3") (pin "11") (pinfunction "CBUS1_11") (pintype "bidirectional"))
      (node (ref "R15") (pin "2") (pinfunction "2_2") (pintype "passive"))
    )
    (net (code "72") (name "Net-(IC3-CBUS2)") (class "Default")
      (node (ref "IC3") (pin "5") (pinfunction "CBUS2_5") (pintype "bidirectional"))
      (node (ref "R14") (pin "2") (pinfunction "2_2") (pintype "passive"))
    )
    (net (code "73") (name "Net-(IC3-USBDM)") (class "Default")
      (node (ref "IC3") (pin "7") (pinfunction "USBDM_7") (pintype "bidirectional"))
      (node (ref "R13") (pin "1") (pinfunction "1_1") (pintype "passive"))
    )
    (net (code "74") (name "Net-(IC3-USBDP)") (class "Default")
      (node (ref "IC3") (pin "6") (pinfunction "USBDP_6") (pintype "bidirectional"))
      (node (ref "R16") (pin "1") (pinfunction "1_1") (pintype "passive"))
    )
    (net (code "75") (name "Net-(LCD1-BK)") (class "Default")
      (node (ref "LCD1") (pin "16") (pinfunction "BK_16") (pintype "bidirectional"))
      (node (ref "R11") (pin "1") (pinfunction "1_1") (pintype "passive"))
    )
    (net (code "76") (name "Net-(LCD1-VO)") (class "Default")
      (node (ref "LCD1") (pin "3") (pinfunction "VO_3") (pintype "bidirectional"))
      (node (ref "VR1") (pin "S") (pinfunction "S_S") (pintype "passive"))
    )
    (net (code "77") (name "Net-(LED1-PadC)") (class "Default")
      (node (ref "LED1") (pin "C") (pinfunction "C_C") (pintype "passive"))
      (node (ref "R10") (pin "1") (pinfunction "1_1") (pintype "passive"))
    )
    (net (code "78") (name "Net-(LED2-PadC)") (class "Default")
      (node (ref "LED2") (pin "C") (pinfunction "C_C") (pintype "passive"))
      (node (ref "R14") (pin "1") (pinfunction "1_1") (pintype "passive"))
    )
    (net (code "79") (name "Net-(LED3-PadC)") (class "Default")
      (node (ref "LED3") (pin "C") (pinfunction "C_C") (pintype "passive"))
      (node (ref "R15") (pin "1") (pinfunction "1_1") (pintype "passive"))
    )
    (net (code "80") (name "Net-(Q3-D)") (class "Default")
      (node (ref "Q3") (pin "3") (pinfunction "D_3") (pintype "passive"))
      (node (ref "R11") (pin "2") (pinfunction "2_2") (pintype "passive"))
    )
    (net (code "81") (name "unconnected-(IC2-(ADC5{slash}TMS)PF5-Pad92)") (class "Default")
      (node (ref "IC2") (pin "92") (pinfunction "(ADC5/TMS)PF5_92") (pintype "bidirectional"))
    )
    (net (code "82") (name "unconnected-(IC2-(ADC6{slash}TDO)PF6-Pad91)") (class "Default")
      (node (ref "IC2") (pin "91") (pinfunction "(ADC6/TDO)PF6_91") (pintype "bidirectional"))
    )
    (net (code "83") (name "unconnected-(IC2-(ADC7{slash}TDI)PF7-Pad90)") (class "Default")
      (node (ref "IC2") (pin "90") (pinfunction "(ADC7/TDI)PF7_90") (pintype "bidirectional"))
    )
    (net (code "84") (name "unconnected-(IC2-(CLKO{slash}ICP3{slash}INT7)PE7-Pad9)") (class "Default")
      (node (ref "IC2") (pin "9") (pinfunction "(CLKO/ICP3/INT7)PE7_9") (pintype "bidirectional"))
    )
    (net (code "85") (name "unconnected-(IC2-(ICP1)PD4-Pad47)") (class "Default")
      (node (ref "IC2") (pin "47") (pinfunction "(ICP1)PD4_47") (pintype "bidirectional"))
    )
    (net (code "86") (name "unconnected-(IC2-(SS{slash}PCINT0)PB0-Pad19)") (class "Default")
      (node (ref "IC2") (pin "19") (pinfunction "(SS/PCINT0)PB0_19") (pintype "bidirectional"))
    )
    (net (code "87") (name "unconnected-(IC2-(T1)PD6-Pad49)") (class "Default")
      (node (ref "IC2") (pin "49") (pinfunction "(T1)PD6_49") (pintype "bidirectional"))
    )
    (net (code "88") (name "unconnected-(IC2-(T3{slash}INT6)PE6-Pad8)") (class "Default")
      (node (ref "IC2") (pin "8") (pinfunction "(T3/INT6)PE6_8") (pintype "bidirectional"))
    )
    (net (code "89") (name "unconnected-(IC2-(TOSC1)PG4-Pad29)") (class "Default")
      (node (ref "IC2") (pin "29") (pinfunction "(TOSC1)PG4_29") (pintype "bidirectional"))
    )
    (net (code "90") (name "unconnected-(IC2-(TOSC2)PG3-Pad28)") (class "Default")
      (node (ref "IC2") (pin "28") (pinfunction "(TOSC2)PG3_28") (pintype "bidirectional"))
    )
    (net (code "91") (name "unconnected-(IC2-(XCK0{slash}AIN0)PE2-Pad4)") (class "Default")
      (node (ref "IC2") (pin "4") (pinfunction "(XCK0/AIN0)PE2_4") (pintype "bidirectional"))
    )
    (net (code "92") (name "unconnected-(IC2-(XCK1)PD5-Pad48)") (class "Default")
      (node (ref "IC2") (pin "48") (pinfunction "(XCK1)PD5_48") (pintype "bidirectional"))
    )
    (net (code "93") (name "unconnected-(IC2-PH2(XCK2)-Pad14)") (class "Default")
      (node (ref "IC2") (pin "14") (pinfunction "PH2(XCK2)_14") (pintype "bidirectional"))
    )
    (net (code "94") (name "unconnected-(IC2-PH7(T4)-Pad27)") (class "Default")
      (node (ref "IC2") (pin "27") (pinfunction "PH7(T4)_27") (pintype "bidirectional"))
    )
    (net (code "95") (name "unconnected-(IC2-PJ2(XCK3{slash}PCINT11)-Pad65)") (class "Default")
      (node (ref "IC2") (pin "65") (pinfunction "PJ2(XCK3/PCINT11)_65") (pintype "bidirectional"))
    )
    (net (code "96") (name "unconnected-(IC2-PJ3(PCINT12)-Pad66)") (class "Default")
      (node (ref "IC2") (pin "66") (pinfunction "PJ3(PCINT12)_66") (pintype "bidirectional"))
    )
    (net (code "97") (name "unconnected-(IC2-PJ4(PCINT13)-Pad67)") (class "Default")
      (node (ref "IC2") (pin "67") (pinfunction "PJ4(PCINT13)_67") (pintype "bidirectional"))
    )
    (net (code "98") (name "unconnected-(IC2-PJ5(PCINT14)-Pad68)") (class "Default")
      (node (ref "IC2") (pin "68") (pinfunction "PJ5(PCINT14)_68") (pintype "bidirectional"))
    )
    (net (code "99") (name "unconnected-(IC2-PJ6(PCINT15)-Pad69)") (class "Default")
      (node (ref "IC2") (pin "69") (pinfunction "PJ6(PCINT15)_69") (pintype "bidirectional"))
    )
    (net (code "100") (name "unconnected-(IC2-PJ7-Pad79)") (class "Default")
      (node (ref "IC2") (pin "79") (pinfunction "PJ7_79") (pintype "bidirectional"))
    )
    (net (code "101") (name "unconnected-(IC2-PK0(ADC8{slash}PCINT16)-Pad89)") (class "Default")
      (node (ref "IC2") (pin "89") (pinfunction "PK0(ADC8/PCINT16)_89") (pintype "bidirectional"))
    )
    (net (code "102") (name "unconnected-(IC2-PK1(ADC9{slash}PCINT17)-Pad88)") (class "Default")
      (node (ref "IC2") (pin "88") (pinfunction "PK1(ADC9/PCINT17)_88") (pintype "bidirectional"))
    )
    (net (code "103") (name "unconnected-(IC2-PK2(ADC10{slash}PCINT18)-Pad87)") (class "Default")
      (node (ref "IC2") (pin "87") (pinfunction "PK2(ADC10/PCINT18)_87") (pintype "bidirectional"))
    )
    (net (code "104") (name "unconnected-(IC2-PK3(ADC11{slash}PCINT19)-Pad86)") (class "Default")
      (node (ref "IC2") (pin "86") (pinfunction "PK3(ADC11/PCINT19)_86") (pintype "bidirectional"))
    )
    (net (code "105") (name "unconnected-(IC2-PK4(ADC12{slash}PCINT20)-Pad85)") (class "Default")
      (node (ref "IC2") (pin "85") (pinfunction "PK4(ADC12/PCINT20)_85") (pintype "bidirectional"))
    )
    (net (code "106") (name "unconnected-(IC2-PK5(ADC13{slash}PCINT21)-Pad84)") (class "Default")
      (node (ref "IC2") (pin "84") (pinfunction "PK5(ADC13/PCINT21)_84") (pintype "bidirectional"))
    )
    (net (code "107") (name "unconnected-(IC2-PK6(ADC14{slash}PCINT22)-Pad83)") (class "Default")
      (node (ref "IC2") (pin "83") (pinfunction "PK6(ADC14/PCINT22)_83") (pintype "bidirectional"))
    )
    (net (code "108") (name "unconnected-(IC2-PK7(ADC15{slash}PCINT23)-Pad82)") (class "Default")
      (node (ref "IC2") (pin "82") (pinfunction "PK7(ADC15/PCINT23)_82") (pintype "bidirectional"))
    )
    (net (code "109") (name "unconnected-(IC2-PL0(ICP4)-Pad35)") (class "Default")
      (node (ref "IC2") (pin "35") (pinfunction "PL0(ICP4)_35") (pintype "bidirectional"))
    )
    (net (code "110") (name "unconnected-(IC2-PL1(ICP5)-Pad36)") (class "Default")
      (node (ref "IC2") (pin "36") (pinfunction "PL1(ICP5)_36") (pintype "bidirectional"))
    )
    (net (code "111") (name "unconnected-(IC2-PL2(T5)-Pad37)") (class "Default")
      (node (ref "IC2") (pin "37") (pinfunction "PL2(T5)_37") (pintype "bidirectional"))
    )
    (net (code "112") (name "unconnected-(IC2-PL3(OC5A)-Pad38)") (class "Default")
      (node (ref "IC2") (pin "38") (pinfunction "PL3(OC5A)_38") (pintype "bidirectional"))
    )
    (net (code "113") (name "unconnected-(IC3-CBUS0-Pad12)") (class "Default")
      (node (ref "IC3") (pin "12") (pinfunction "CBUS0_12") (pintype "bidirectional"))
    )
    (net (code "114") (name "unconnected-(IC3-CBUS3-Pad14)") (class "Default")
      (node (ref "IC3") (pin "14") (pinfunction "CBUS3_14") (pintype "bidirectional"))
    )
    (net (code "115") (name "unconnected-(IC3-RTS#-Pad16)") (class "Default")
      (node (ref "IC3") (pin "16") (pinfunction "RTS#_16") (pintype "bidirectional"))
    )
    (net (code "116") (name "unconnected-(J3-CARD_DETECT1-PadCD2)") (class "Default")
      (node (ref "J3") (pin "CD2") (pinfunction "CARD_DETECT1_CD2") (pintype "passive"))
    )
    (net (code "117") (name "unconnected-(J3-DAT1-Pad8)") (class "Default")
      (node (ref "J3") (pin "8") (pinfunction "DAT1_8") (pintype "bidirectional"))
    )
    (net (code "118") (name "unconnected-(J3-DAT2-Pad1)") (class "Default")
      (node (ref "J3") (pin "1") (pinfunction "DAT2_1") (pintype "bidirectional"))
    )
    (net (code "119") (name "unconnected-(LCD1-D0-Pad7)") (class "Default")
      (node (ref "LCD1") (pin "7") (pinfunction "D0_7") (pintype "bidirectional"))
    )
    (net (code "120") (name "unconnected-(LCD1-D1-Pad8)") (class "Default")
      (node (ref "LCD1") (pin "8") (pinfunction "D1_8") (pintype "bidirectional"))
    )
    (net (code "121") (name "unconnected-(LCD1-D2-Pad9)") (class "Default")
      (node (ref "LCD1") (pin "9") (pinfunction "D2_9") (pintype "bidirectional"))
    )
    (net (code "122") (name "unconnected-(LCD1-D3-Pad10)") (class "Default")
      (node (ref "LCD1") (pin "10") (pinfunction "D3_10") (pintype "bidirectional"))
    )
  )
)
